# TopBee2_0V.net
KiCad netlist of a schematic drawn in EAGLE
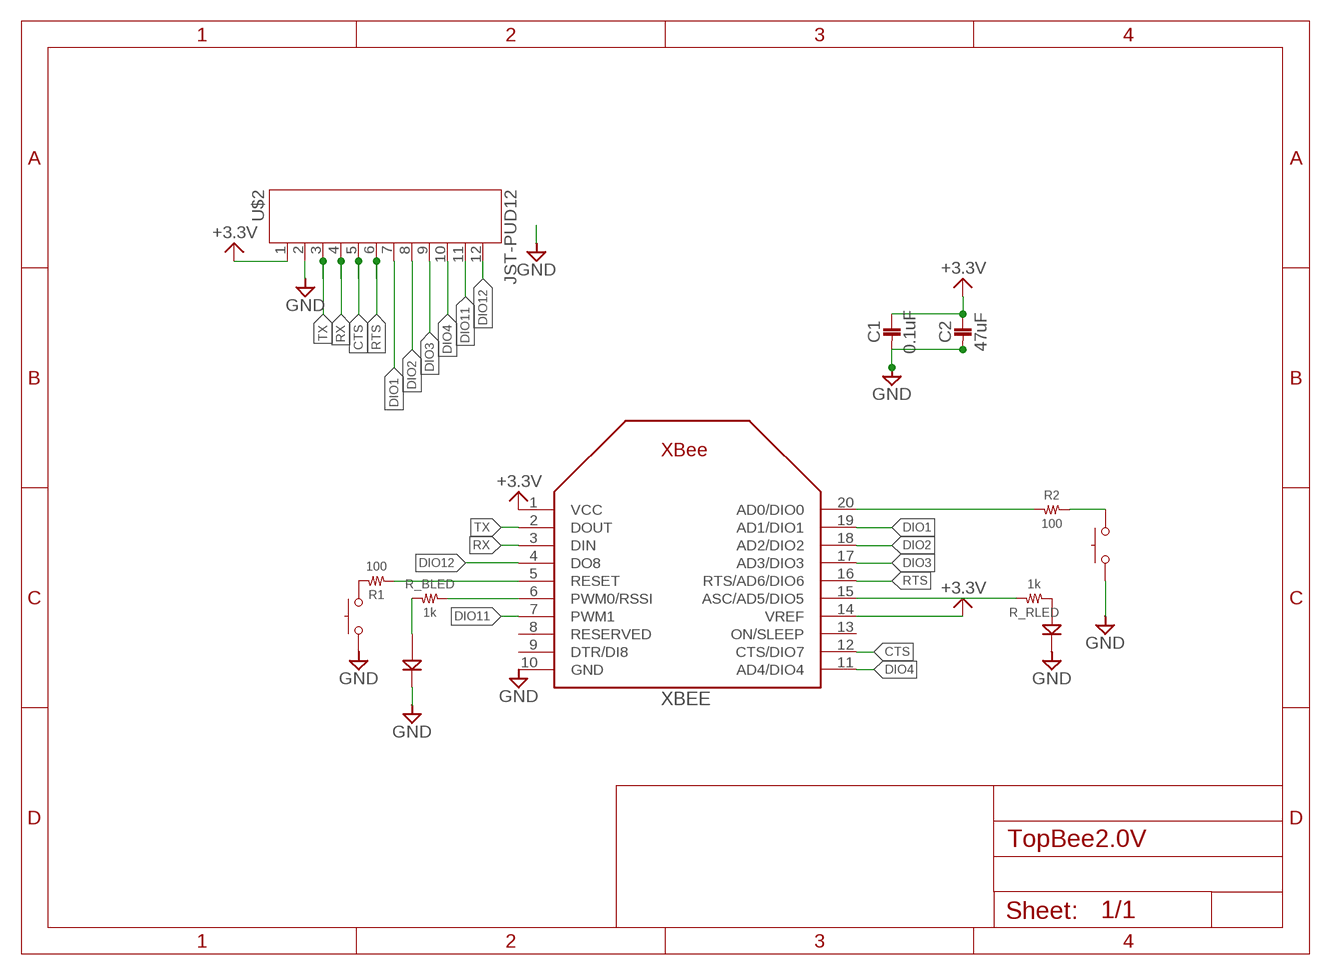
[diagram p0: schematic, sheet 1]

(export (version "E")
  (design (tool "Eeschema 10.0.6"))
  (components
    (comp (ref "C1")
      (value "0.1uF")
      (footprint "eagle-import:1608")
      (libsource (lib "eagle-import") (part "1608"))
    )
    (comp (ref "C2")
      (value "47uF")
      (footprint "eagle-import:3225")
      (libsource (lib "eagle-import") (part "3225"))
    )
    (comp (ref "COMM")
      (value "SKRPACE010")
      (footprint "eagle-import:SKRP")
      (libsource (lib "eagle-import") (part "SKRPACE010"))
    )
    (comp (ref "LED_B")
      (value "1608")
      (footprint "eagle-import:1608")
      (libsource (lib "eagle-import") (part "10_LED_1608"))
    )
    (comp (ref "LED_R")
      (value "1608")
      (footprint "eagle-import:1608")
      (libsource (lib "eagle-import") (part "10_LED_1608"))
    )
    (comp (ref "R1")
      (value "100")
      (footprint "eagle-import:1608")
      (libsource (lib "eagle-import") (part "RESISTOR__SMD"))
    )
    (comp (ref "R2")
      (value "100")
      (footprint "eagle-import:1608")
      (libsource (lib "eagle-import") (part "RESISTOR__SMD"))
    )
    (comp (ref "RESET")
      (value "SKRPACE010")
      (footprint "eagle-import:SKRP")
      (libsource (lib "eagle-import") (part "SKRPACE010"))
    )
    (comp (ref "R_BLED")
      (value "1k")
      (footprint "eagle-import:1608")
      (libsource (lib "eagle-import") (part "RESISTOR__SMD"))
    )
    (comp (ref "R_RLED")
      (value "1k")
      (footprint "eagle-import:1608")
      (libsource (lib "eagle-import") (part "RESISTOR__SMD"))
    )
    (comp (ref "U$2")
      (value "JST-PUD12")
      (footprint "eagle-import:JST-PUD12")
      (libsource (lib "eagle-import") (part "JST-PUD12"))
    )
    (comp (ref "XBEE")
      (value "XBEE")
      (footprint "eagle-import:XBEE")
      (libsource (lib "eagle-import") (part "XBEE"))
    )
  )
  (nets
    (net (code "1") (name "+3.3V") (class "Default")
      (node (ref "C1") (pin "P$1") (pinfunction "1_P$1") (pintype "passive"))
      (node (ref "C2") (pin "P$1") (pinfunction "1_P$1") (pintype "passive"))
      (node (ref "U$2") (pin "1") (pinfunction "1_1") (pintype "passive"))
      (node (ref "XBEE") (pin "1") (pinfunction "VCC_1") (pintype "power_in"))
      (node (ref "XBEE") (pin "14") (pinfunction "VREF_14") (pintype "input"))
    )
    (net (code "2") (name "CTS") (class "Default")
      (node (ref "U$2") (pin "5") (pinfunction "5_5") (pintype "passive"))
      (node (ref "XBEE") (pin "12") (pinfunction "CTS/DIO7_12") (pintype "bidirectional"))
    )
    (net (code "3") (name "DIO1") (class "Default")
      (node (ref "U$2") (pin "7") (pinfunction "7_7") (pintype "passive"))
      (node (ref "XBEE") (pin "19") (pinfunction "AD1/DIO1_19") (pintype "bidirectional"))
    )
    (net (code "4") (name "DIO2") (class "Default")
      (node (ref "U$2") (pin "8") (pinfunction "8_8") (pintype "passive"))
      (node (ref "XBEE") (pin "18") (pinfunction "AD2/DIO2_18") (pintype "bidirectional"))
    )
    (net (code "5") (name "DIO3") (class "Default")
      (node (ref "U$2") (pin "9") (pinfunction "9_9") (pintype "passive"))
      (node (ref "XBEE") (pin "17") (pinfunction "AD3/DIO3_17") (pintype "bidirectional"))
    )
    (net (code "6") (name "DIO4") (class "Default")
      (node (ref "U$2") (pin "10") (pinfunction "10_10") (pintype "passive"))
      (node (ref "XBEE") (pin "11") (pinfunction "AD4/DIO4_11") (pintype "bidirectional"))
    )
    (net (code "7") (name "DIO11") (class "Default")
      (node (ref "U$2") (pin "11") (pinfunction "11_11") (pintype "passive"))
      (node (ref "XBEE") (pin "7") (pinfunction "PWM1_7") (pintype "output"))
    )
    (net (code "8") (name "DIO12") (class "Default")
      (node (ref "U$2") (pin "12") (pinfunction "12_12") (pintype "passive"))
      (node (ref "XBEE") (pin "4") (pinfunction "DO8_4") (pintype "output"))
    )
    (net (code "9") (name "GND") (class "Default")
      (node (ref "C1") (pin "P$2") (pinfunction "2_P$2") (pintype "passive"))
      (node (ref "C2") (pin "P$2") (pinfunction "2_P$2") (pintype "passive"))
      (node (ref "COMM") (pin "3") (pinfunction "P$2_3") (pintype "bidirectional"))
      (node (ref "COMM") (pin "4") (pinfunction "P$2_4") (pintype "bidirectional"))
      (node (ref "LED_B") (pin "2") (pinfunction "K_2") (pintype "bidirectional"))
      (node (ref "LED_R") (pin "2") (pinfunction "K_2") (pintype "bidirectional"))
      (node (ref "RESET") (pin "3") (pinfunction "P$2_3") (pintype "bidirectional"))
      (node (ref "RESET") (pin "4") (pinfunction "P$2_4") (pintype "bidirectional"))
      (node (ref "U$2") (pin "2") (pinfunction "2_2") (pintype "passive"))
      (node (ref "XBEE") (pin "10") (pinfunction "GND_10") (pintype "power_in"))
    )
    (net (code "10") (name "Net-(LED_B-A)") (class "Default")
      (node (ref "LED_B") (pin "1") (pinfunction "A_1") (pintype "bidirectional"))
      (node (ref "R_BLED") (pin "1") (pinfunction "P$1_1") (pintype "passive"))
    )
    (net (code "11") (name "Net-(LED_R-A)") (class "Default")
      (node (ref "LED_R") (pin "1") (pinfunction "A_1") (pintype "bidirectional"))
      (node (ref "R_RLED") (pin "1") (pinfunction "P$1_1") (pintype "passive"))
    )
    (net (code "12") (name "Net-(R1-P$1)") (class "Default")
      (node (ref "R1") (pin "1") (pinfunction "P$1_1") (pintype "passive"))
      (node (ref "XBEE") (pin "5") (pinfunction "RESET_5") (pintype "input"))
    )
    (net (code "13") (name "Net-(R1-P$2)") (class "Default")
      (node (ref "R1") (pin "2") (pinfunction "P$2_2") (pintype "passive"))
      (node (ref "RESET") (pin "1") (pinfunction "P$1_1") (pintype "bidirectional"))
      (node (ref "RESET") (pin "2") (pinfunction "P$1_2") (pintype "bidirectional"))
    )
    (net (code "14") (name "Net-(R2-P$1)") (class "Default")
      (node (ref "R2") (pin "1") (pinfunction "P$1_1") (pintype "passive"))
      (node (ref "XBEE") (pin "20") (pinfunction "AD0/DIO0_20") (pintype "bidirectional"))
    )
    (net (code "15") (name "Net-(R2-P$2)") (class "Default")
      (node (ref "COMM") (pin "1") (pinfunction "P$1_1") (pintype "bidirectional"))
      (node (ref "COMM") (pin "2") (pinfunction "P$1_2") (pintype "bidirectional"))
      (node (ref "R2") (pin "2") (pinfunction "P$2_2") (pintype "passive"))
    )
    (net (code "16") (name "Net-(R_BLED-P$2)") (class "Default")
      (node (ref "R_BLED") (pin "2") (pinfunction "P$2_2") (pintype "passive"))
      (node (ref "XBEE") (pin "6") (pinfunction "PWM0/RSSI_6") (pintype "output"))
    )
    (net (code "17") (name "Net-(R_RLED-P$2)") (class "Default")
      (node (ref "R_RLED") (pin "2") (pinfunction "P$2_2") (pintype "passive"))
      (node (ref "XBEE") (pin "15") (pinfunction "ASC/AD5/DIO5_15") (pintype "bidirectional"))
    )
    (net (code "18") (name "RTS") (class "Default")
      (node (ref "U$2") (pin "6") (pinfunction "6_6") (pintype "passive"))
      (node (ref "XBEE") (pin "16") (pinfunction "RTS/AD6/DIO6_16") (pintype "bidirectional"))
    )
    (net (code "19") (name "RX") (class "Default")
      (node (ref "U$2") (pin "4") (pinfunction "4_4") (pintype "passive"))
      (node (ref "XBEE") (pin "3") (pinfunction "DIN_3") (pintype "input"))
    )
    (net (code "20") (name "TX") (class "Default")
      (node (ref "U$2") (pin "3") (pinfunction "3_3") (pintype "passive"))
      (node (ref "XBEE") (pin "2") (pinfunction "DOUT_2") (pintype "output"))
    )
    (net (code "21") (name "unconnected-(XBEE-DTR{slash}DI8-Pad9)") (class "Default")
      (node (ref "XBEE") (pin "9") (pinfunction "DTR/DI8_9") (pintype "input"))
    )
    (net (code "22") (name "unconnected-(XBEE-ON{slash}SLEEP-Pad13)") (class "Default")
      (node (ref "XBEE") (pin "13") (pinfunction "ON/SLEEP_13") (pintype "output"))
    )
    (net (code "23") (name "unconnected-(XBEE-RESERVED-Pad8)") (class "Default")
      (node (ref "XBEE") (pin "8") (pinfunction "RESERVED_8") (pintype "no_connect"))
    )
  )
)
